# Arduino_Engine_Room.net
KiCad netlist of a schematic drawn in EAGLE
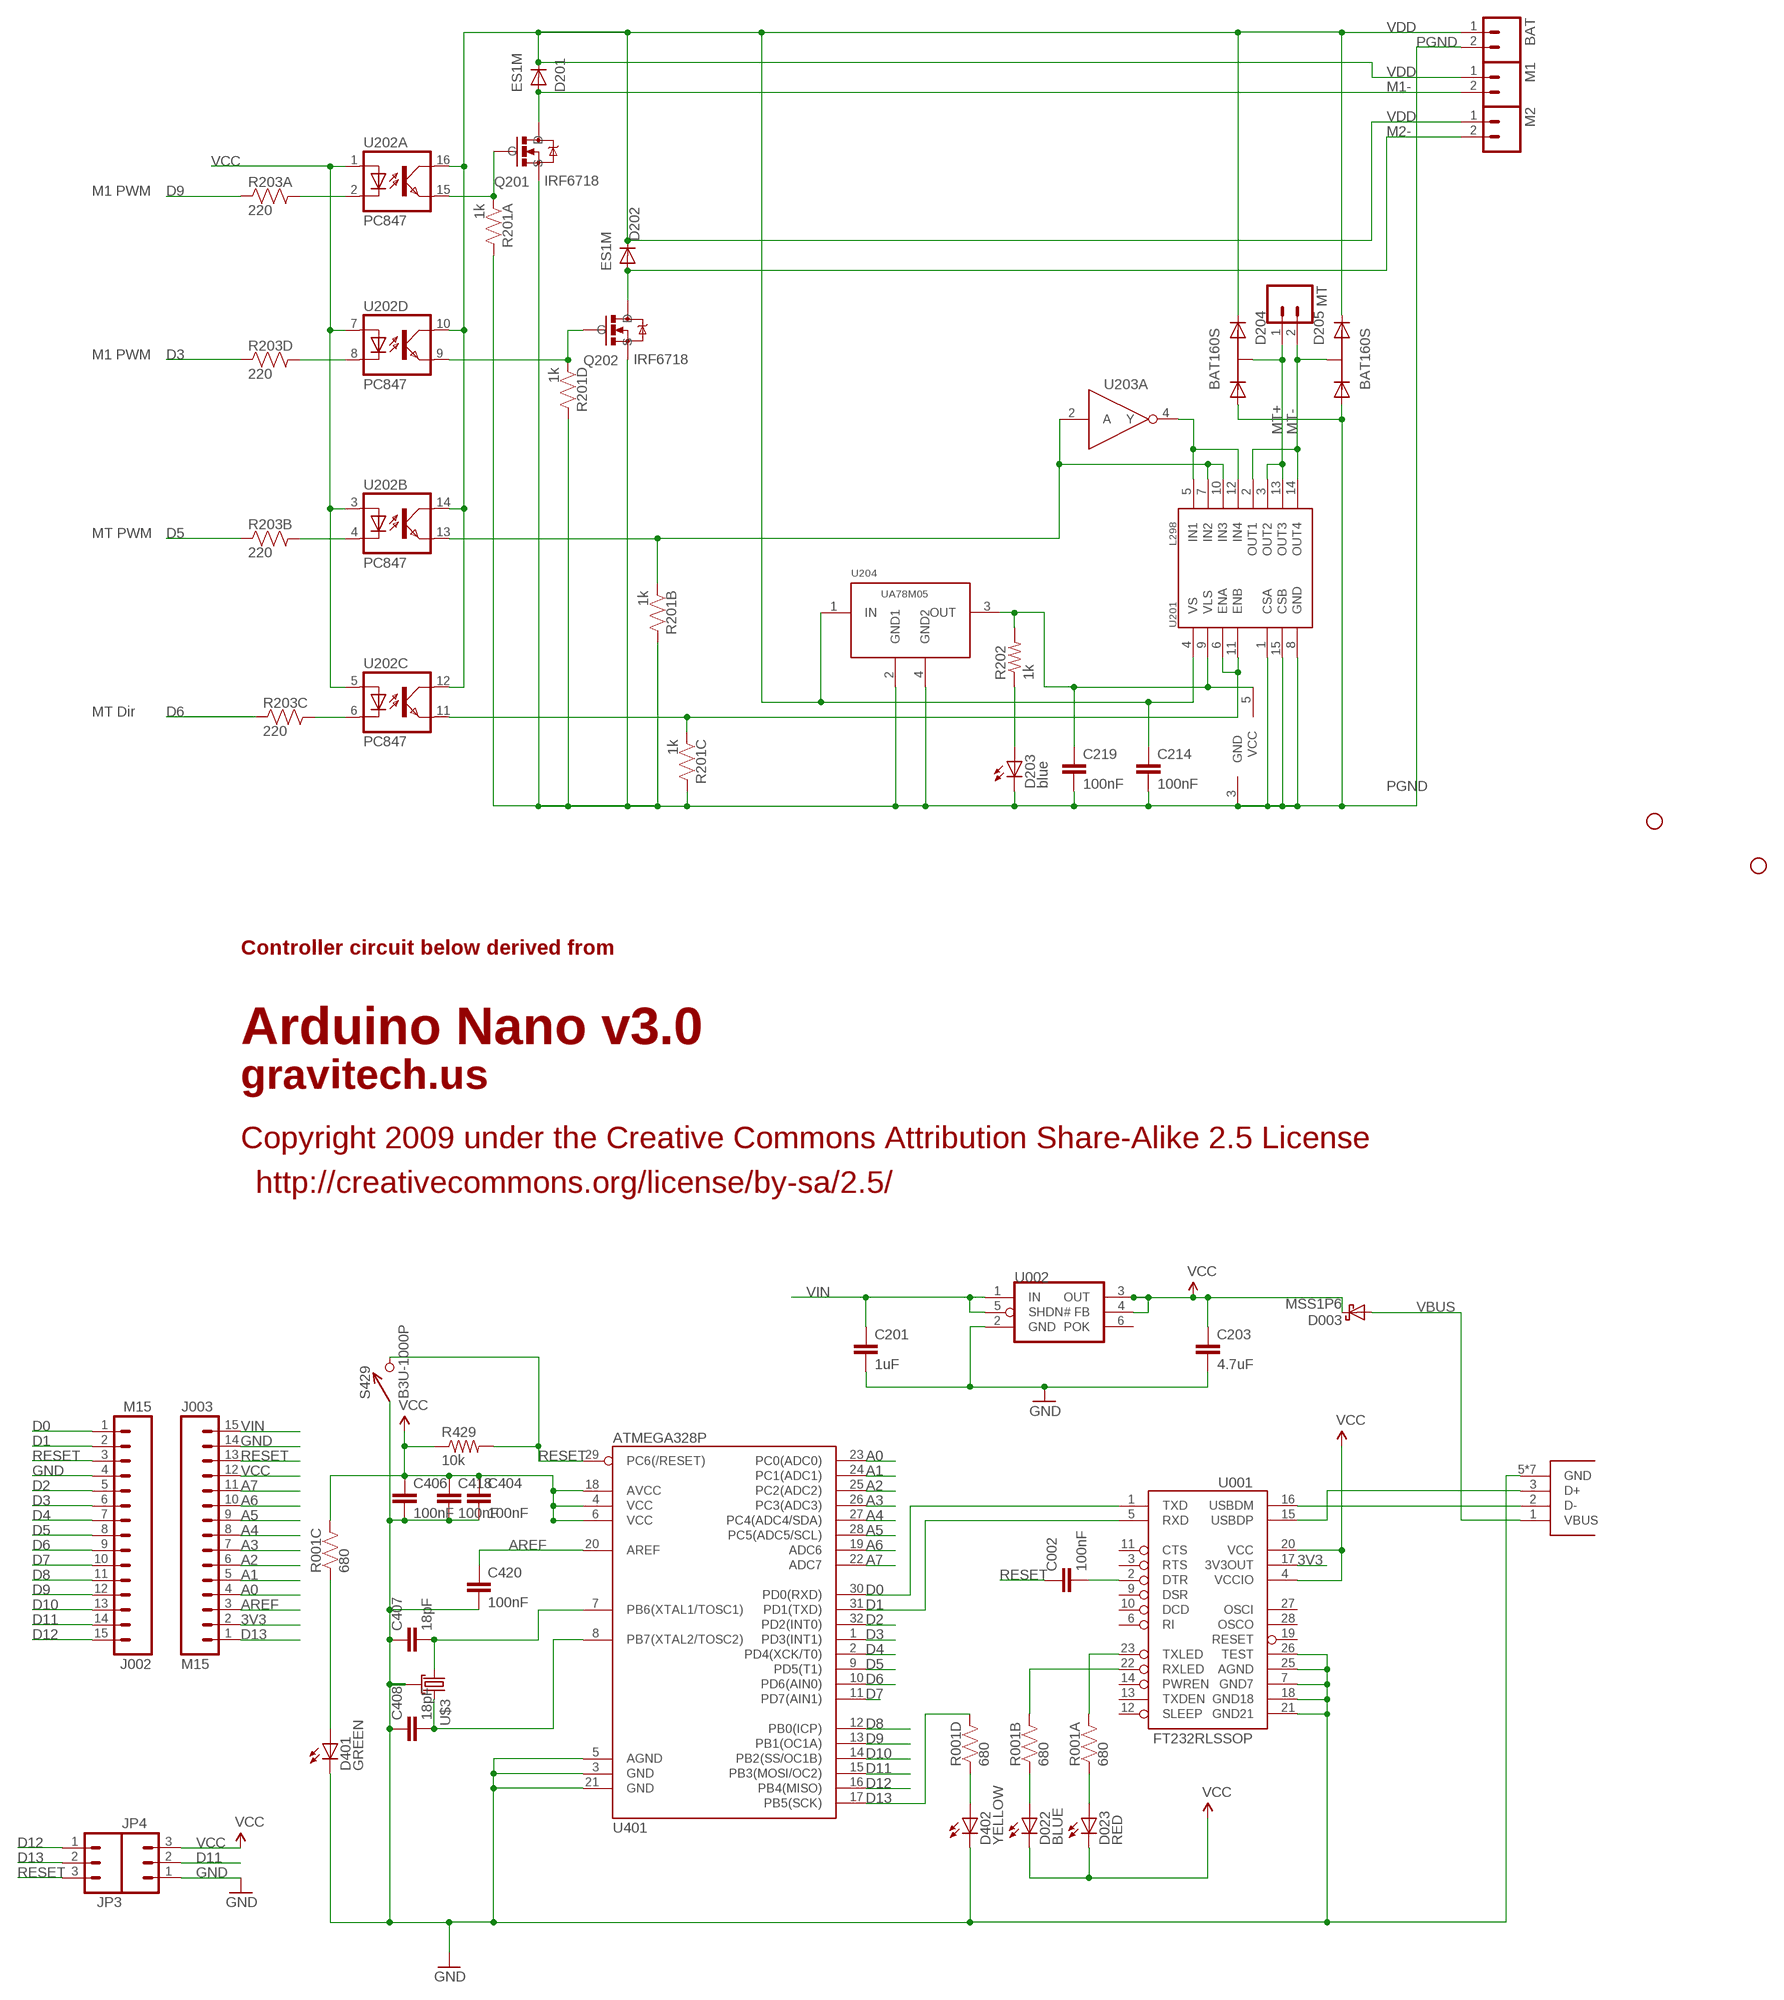
[diagram p0: schematic, sheet 1]

(export (version "E")
  (design (tool "Eeschema 10.0.6"))
  (components
    (comp (ref "BAT")
      (value "M02PTH4")
      (footprint "eagle-import:1X02_XTRA_BIG")
      (libsource (lib "eagle-import") (part "M02PTH4"))
    )
    (comp (ref "C002")
      (value "100nF")
      (footprint "eagle-import:0402-CAP")
      (libsource (lib "eagle-import") (part "CAP0402-CAP"))
    )
    (comp (ref "C201")
      (value "1uF")
      (footprint "eagle-import:0402-CAP")
      (libsource (lib "eagle-import") (part "CAP0402-CAP"))
    )
    (comp (ref "C203")
      (value "4.7uF")
      (footprint "eagle-import:0402-CAP")
      (libsource (lib "eagle-import") (part "CAP0402-CAP"))
    )
    (comp (ref "C214")
      (value "100nF")
      (footprint "eagle-import:0402-CAP")
      (libsource (lib "eagle-import") (part "CAP0402-CAP"))
    )
    (comp (ref "C219")
      (value "100nF")
      (footprint "eagle-import:0402-CAP")
      (libsource (lib "eagle-import") (part "CAP0402-CAP"))
    )
    (comp (ref "C404")
      (value "100nF")
      (footprint "eagle-import:0402-CAP")
      (libsource (lib "eagle-import") (part "CAP0402-CAP"))
    )
    (comp (ref "C406")
      (value "100nF")
      (footprint "eagle-import:0402-CAP")
      (libsource (lib "eagle-import") (part "CAP0402-CAP"))
    )
    (comp (ref "C407")
      (value "18pF")
      (footprint "eagle-import:0402-CAP")
      (libsource (lib "eagle-import") (part "CAP0402-CAP"))
    )
    (comp (ref "C408")
      (value "18pF")
      (footprint "eagle-import:0402-CAP")
      (libsource (lib "eagle-import") (part "CAP0402-CAP"))
    )
    (comp (ref "C418")
      (value "100nF")
      (footprint "eagle-import:0402-CAP")
      (libsource (lib "eagle-import") (part "CAP0402-CAP"))
    )
    (comp (ref "C420")
      (value "100nF")
      (footprint "eagle-import:0402-CAP")
      (libsource (lib "eagle-import") (part "CAP0402-CAP"))
    )
    (comp (ref "D003")
      (value "MSS1P6")
      (footprint "eagle-import:MICROSMP")
      (libsource (lib "eagle-import") (part "MSS1P6"))
    )
    (comp (ref "D022")
      (value "BLUE")
      (footprint "eagle-import:LED-0603")
      (libsource (lib "eagle-import") (part "SparkFun-LED_LED0603"))
    )
    (comp (ref "D023")
      (value "RED")
      (footprint "eagle-import:LED-0603")
      (libsource (lib "eagle-import") (part "SparkFun-LED_LED0603"))
    )
    (comp (ref "D201")
      (value "ES1M")
      (footprint "eagle-import:DO-214AC")
      (libsource (lib "eagle-import") (part "DIODE-DO-214AC"))
    )
    (comp (ref "D202")
      (value "ES1M")
      (footprint "eagle-import:DO-214AC")
      (libsource (lib "eagle-import") (part "DIODE-DO-214AC"))
    )
    (comp (ref "D203")
      (value "blue")
      (footprint "eagle-import:LED-0603")
      (libsource (lib "eagle-import") (part "LED0603"))
    )
    (comp (ref "D204")
      (value "BAT160S")
      (footprint "eagle-import:SOT-223")
      (libsource (lib "eagle-import") (part "BAT160S"))
    )
    (comp (ref "D205")
      (value "BAT160S")
      (footprint "eagle-import:SOT-223")
      (libsource (lib "eagle-import") (part "BAT160S"))
    )
    (comp (ref "D401")
      (value "GREEN")
      (footprint "eagle-import:LED-0603")
      (libsource (lib "eagle-import") (part "SparkFun-LED_LED0603"))
    )
    (comp (ref "D402")
      (value "YELLOW")
      (footprint "eagle-import:LED-0603")
      (libsource (lib "eagle-import") (part "SparkFun-LED_LED0603"))
    )
    (comp (ref "J001")
      (value "USB_MICROB_JST")
      (footprint "eagle-import:UB-MC5BR3-SD204-4S")
      (libsource (lib "eagle-import") (part "USB_MICROB_JST"))
    )
    (comp (ref "J002")
      (value "M15")
      (footprint "eagle-import:1X15")
      (libsource (lib "eagle-import") (part "M15"))
    )
    (comp (ref "J003")
      (value "M15")
      (footprint "eagle-import:1X15")
      (libsource (lib "eagle-import") (part "M15"))
    )
    (comp (ref "JP1")
      (value "STAND-OFF")
      (footprint "eagle-import:STAND-OFF")
      (libsource (lib "eagle-import") (part "STAND-OFF"))
    )
    (comp (ref "JP2")
      (value "STAND-OFF")
      (footprint "eagle-import:STAND-OFF")
      (libsource (lib "eagle-import") (part "STAND-OFF"))
    )
    (comp (ref "JP3")
      (value "M03PTH")
      (footprint "eagle-import:1X03")
      (libsource (lib "eagle-import") (part "M03PTH"))
    )
    (comp (ref "JP4")
      (value "M03PTH")
      (footprint "eagle-import:1X03")
      (libsource (lib "eagle-import") (part "M03PTH"))
    )
    (comp (ref "M1")
      (value "M02PTH4")
      (footprint "eagle-import:1X02_XTRA_BIG")
      (libsource (lib "eagle-import") (part "M02PTH4"))
    )
    (comp (ref "M2")
      (value "M02PTH4")
      (footprint "eagle-import:1X02_XTRA_BIG")
      (libsource (lib "eagle-import") (part "M02PTH4"))
    )
    (comp (ref "MT")
      (value "M02PTH")
      (footprint "eagle-import:1X02")
      (libsource (lib "eagle-import") (part "M02PTH"))
    )
    (comp (ref "Q201")
      (value "IRF6718")
      (footprint "eagle-import:DIRECTFET_L6")
      (libsource (lib "eagle-import") (part "IRF6718"))
    )
    (comp (ref "Q202")
      (value "IRF6718")
      (footprint "eagle-import:DIRECTFET_L6")
      (libsource (lib "eagle-import") (part "IRF6718"))
    )
    (comp (ref "R001")
      (value "680")
      (footprint "eagle-import:CRA04")
      (fields (field (name "DIGIKEY") "CRA4S8680CT-ND"))
      (libsource (lib "eagle-import") (part "RP404"))
    )
    (comp (ref "R201")
      (value "1k")
      (footprint "eagle-import:CRA04")
      (libsource (lib "eagle-import") (part "RP404"))
    )
    (comp (ref "R202")
      (value "1k")
      (footprint "eagle-import:0402-RES")
      (libsource (lib "eagle-import") (part "RESISTOR0402-RES"))
    )
    (comp (ref "R203")
      (value "220")
      (footprint "eagle-import:CRA04")
      (libsource (lib "eagle-import") (part "RP404"))
    )
    (comp (ref "R429")
      (value "10k")
      (footprint "eagle-import:0402-RES")
      (libsource (lib "eagle-import") (part "SparkFun-Passives_RESISTOR0402-RES"))
    )
    (comp (ref "S429")
      (value "B3U-1000P")
      (footprint "eagle-import:B3U-1000P")
      (libsource (lib "eagle-import") (part "B3U-1000P"))
    )
    (comp (ref "U$3")
      (value "CX2520")
      (footprint "eagle-import:CRYSTAL_SMD_2MM_2_5MM")
      (libsource (lib "eagle-import") (part "CX2520"))
    )
    (comp (ref "U001")
      (value "FT232RLSSOP")
      (footprint "eagle-import:SSOP28DB")
      (libsource (lib "eagle-import") (part "FT232RLSSOP"))
    )
    (comp (ref "U002")
      (value "MAX8881")
      (footprint "eagle-import:SOT-23-6")
      (libsource (lib "eagle-import") (part "MAX8881"))
    )
    (comp (ref "U201")
      (value "L298")
      (footprint "eagle-import:MULTIWATT15")
      (libsource (lib "eagle-import") (part "L298"))
    )
    (comp (ref "U202")
      (value "PC847")
      (footprint "eagle-import:DIL16")
      (libsource (lib "eagle-import") (part "PC847"))
    )
    (comp (ref "U203")
      (value "MC74VHC1G04")
      (footprint "eagle-import:SOT-23-5")
      (libsource (lib "eagle-import") (part "MC74VHC1G04"))
    )
    (comp (ref "U204")
      (value "UA78M05")
      (footprint "eagle-import:SOT223")
      (libsource (lib "eagle-import") (part "UA78M05"))
    )
    (comp (ref "U401")
      (value "ATMEGA328P")
      (footprint "eagle-import:TQFP32-08")
      (libsource (lib "eagle-import") (part "ATMEGA168"))
    )
  )
  (nets
    (net (code "1") (name "/3V3") (class "Default")
      (node (ref "J003") (pin "2") (pinfunction "2_2") (pintype "passive"))
      (node (ref "U001") (pin "17") (pinfunction "3V3OUT_17") (pintype "output"))
    )
    (net (code "2") (name "/A0") (class "Default")
      (node (ref "J003") (pin "4") (pinfunction "4_4") (pintype "passive"))
      (node (ref "U401") (pin "23") (pinfunction "PC0(ADC0)_23") (pintype "bidirectional"))
    )
    (net (code "3") (name "/A1") (class "Default")
      (node (ref "J003") (pin "5") (pinfunction "5_5") (pintype "passive"))
      (node (ref "U401") (pin "24") (pinfunction "PC1(ADC1)_24") (pintype "bidirectional"))
    )
    (net (code "4") (name "/A2") (class "Default")
      (node (ref "J003") (pin "6") (pinfunction "6_6") (pintype "passive"))
      (node (ref "U401") (pin "25") (pinfunction "PC2(ADC2)_25") (pintype "bidirectional"))
    )
    (net (code "5") (name "/A3") (class "Default")
      (node (ref "J003") (pin "7") (pinfunction "7_7") (pintype "passive"))
      (node (ref "U401") (pin "26") (pinfunction "PC3(ADC3)_26") (pintype "bidirectional"))
    )
    (net (code "6") (name "/A4") (class "Default")
      (node (ref "J003") (pin "8") (pinfunction "8_8") (pintype "passive"))
      (node (ref "U401") (pin "27") (pinfunction "PC4(ADC4/SDA)_27") (pintype "bidirectional"))
    )
    (net (code "7") (name "/A5") (class "Default")
      (node (ref "J003") (pin "9") (pinfunction "9_9") (pintype "passive"))
      (node (ref "U401") (pin "28") (pinfunction "PC5(ADC5/SCL)_28") (pintype "bidirectional"))
    )
    (net (code "8") (name "/A6") (class "Default")
      (node (ref "J003") (pin "10") (pinfunction "10_10") (pintype "passive"))
      (node (ref "U401") (pin "19") (pinfunction "ADC6_19") (pintype "bidirectional"))
    )
    (net (code "9") (name "/A7") (class "Default")
      (node (ref "J003") (pin "11") (pinfunction "11_11") (pintype "passive"))
      (node (ref "U401") (pin "22") (pinfunction "ADC7_22") (pintype "bidirectional"))
    )
    (net (code "10") (name "/AREF") (class "Default")
      (node (ref "C420") (pin "1") (pinfunction "1_1") (pintype "passive"))
      (node (ref "J003") (pin "3") (pinfunction "3_3") (pintype "passive"))
      (node (ref "U401") (pin "20") (pinfunction "AREF_20") (pintype "bidirectional"))
    )
    (net (code "11") (name "/D0") (class "Default")
      (node (ref "J002") (pin "1") (pinfunction "1_1") (pintype "passive"))
      (node (ref "U001") (pin "1") (pinfunction "TXD_1") (pintype "output"))
      (node (ref "U401") (pin "30") (pinfunction "PD0(RXD)_30") (pintype "bidirectional"))
    )
    (net (code "12") (name "/D1") (class "Default")
      (node (ref "J002") (pin "2") (pinfunction "2_2") (pintype "passive"))
      (node (ref "U001") (pin "5") (pinfunction "RXD_5") (pintype "input"))
      (node (ref "U401") (pin "31") (pinfunction "PD1(TXD)_31") (pintype "bidirectional"))
    )
    (net (code "13") (name "/D2") (class "Default")
      (node (ref "J002") (pin "5") (pinfunction "5_5") (pintype "passive"))
      (node (ref "U401") (pin "32") (pinfunction "PD2(INT0)_32") (pintype "bidirectional"))
    )
    (net (code "14") (name "/D3") (class "Default")
      (node (ref "J002") (pin "6") (pinfunction "6_6") (pintype "passive"))
      (node (ref "R203") (pin "4") (pinfunction "1_4") (pintype "passive"))
      (node (ref "U401") (pin "1") (pinfunction "PD3(INT1)_1") (pintype "bidirectional"))
    )
    (net (code "15") (name "/D4") (class "Default")
      (node (ref "J002") (pin "7") (pinfunction "7_7") (pintype "passive"))
      (node (ref "U401") (pin "2") (pinfunction "PD4(XCK/T0)_2") (pintype "bidirectional"))
    )
    (net (code "16") (name "/D5") (class "Default")
      (node (ref "J002") (pin "8") (pinfunction "8_8") (pintype "passive"))
      (node (ref "R203") (pin "2") (pinfunction "1_2") (pintype "passive"))
      (node (ref "U401") (pin "9") (pinfunction "PD5(T1)_9") (pintype "bidirectional"))
    )
    (net (code "17") (name "/D6") (class "Default")
      (node (ref "J002") (pin "9") (pinfunction "9_9") (pintype "passive"))
      (node (ref "R203") (pin "3") (pinfunction "1_3") (pintype "passive"))
      (node (ref "U401") (pin "10") (pinfunction "PD6(AIN0)_10") (pintype "bidirectional"))
    )
    (net (code "18") (name "/D7") (class "Default")
      (node (ref "J002") (pin "10") (pinfunction "10_10") (pintype "passive"))
      (node (ref "U401") (pin "11") (pinfunction "PD7(AIN1)_11") (pintype "bidirectional"))
    )
    (net (code "19") (name "/D8") (class "Default")
      (node (ref "J002") (pin "11") (pinfunction "11_11") (pintype "passive"))
      (node (ref "U401") (pin "12") (pinfunction "PB0(ICP)_12") (pintype "bidirectional"))
    )
    (net (code "20") (name "/D9") (class "Default")
      (node (ref "J002") (pin "12") (pinfunction "12_12") (pintype "passive"))
      (node (ref "R203") (pin "1") (pinfunction "1_1") (pintype "passive"))
      (node (ref "U401") (pin "13") (pinfunction "PB1(OC1A)_13") (pintype "bidirectional"))
    )
    (net (code "21") (name "/D10") (class "Default")
      (node (ref "J002") (pin "13") (pinfunction "13_13") (pintype "passive"))
      (node (ref "U401") (pin "14") (pinfunction "PB2(SS/OC1B)_14") (pintype "bidirectional"))
    )
    (net (code "22") (name "/D11") (class "Default")
      (node (ref "J002") (pin "14") (pinfunction "14_14") (pintype "passive"))
      (node (ref "JP4") (pin "2") (pinfunction "2_2") (pintype "passive"))
      (node (ref "U401") (pin "15") (pinfunction "PB3(MOSI/OC2)_15") (pintype "bidirectional"))
    )
    (net (code "23") (name "/D12") (class "Default")
      (node (ref "J002") (pin "15") (pinfunction "15_15") (pintype "passive"))
      (node (ref "JP3") (pin "1") (pinfunction "1_1") (pintype "passive"))
      (node (ref "U401") (pin "16") (pinfunction "PB4(MISO)_16") (pintype "bidirectional"))
    )
    (net (code "24") (name "/D13") (class "Default")
      (node (ref "J003") (pin "1") (pinfunction "1_1") (pintype "passive"))
      (node (ref "JP3") (pin "2") (pinfunction "2_2") (pintype "passive"))
      (node (ref "R001") (pin "5") (pinfunction "2_5") (pintype "passive"))
      (node (ref "U401") (pin "17") (pinfunction "PB5(SCK)_17") (pintype "bidirectional"))
    )
    (net (code "25") (name "/M1-") (class "Default")
      (node (ref "D201") (pin "A") (pinfunction "A_A") (pintype "passive"))
      (node (ref "M1") (pin "2") (pinfunction "2_2") (pintype "passive"))
      (node (ref "Q201") (pin "D1") (pinfunction "D_D1") (pintype "passive"))
      (node (ref "Q201") (pin "D2") (pinfunction "D_D2") (pintype "passive"))
    )
    (net (code "26") (name "/M2-") (class "Default")
      (node (ref "D202") (pin "A") (pinfunction "A_A") (pintype "passive"))
      (node (ref "M2") (pin "2") (pinfunction "2_2") (pintype "passive"))
      (node (ref "Q202") (pin "D1") (pinfunction "D_D1") (pintype "passive"))
      (node (ref "Q202") (pin "D2") (pinfunction "D_D2") (pintype "passive"))
    )
    (net (code "27") (name "/MT+") (class "Default")
      (node (ref "D204") (pin "4") (pinfunction "K1A2_4") (pintype "passive"))
      (node (ref "MT") (pin "1") (pinfunction "1_1") (pintype "passive"))
      (node (ref "U201") (pin "13") (pinfunction "OUT3_13") (pintype "bidirectional"))
      (node (ref "U201") (pin "3") (pinfunction "OUT2_3") (pintype "bidirectional"))
    )
    (net (code "28") (name "/MT-") (class "Default")
      (node (ref "D205") (pin "4") (pinfunction "K1A2_4") (pintype "passive"))
      (node (ref "MT") (pin "2") (pinfunction "2_2") (pintype "passive"))
      (node (ref "U201") (pin "14") (pinfunction "OUT4_14") (pintype "bidirectional"))
      (node (ref "U201") (pin "2") (pinfunction "OUT1_2") (pintype "bidirectional"))
    )
    (net (code "29") (name "/PGND") (class "Default")
      (node (ref "BAT") (pin "2") (pinfunction "2_2") (pintype "passive"))
      (node (ref "C214") (pin "2") (pinfunction "2_2") (pintype "passive"))
      (node (ref "C219") (pin "2") (pinfunction "2_2") (pintype "passive"))
      (node (ref "D203") (pin "C") (pinfunction "C_C") (pintype "passive"))
      (node (ref "D204") (pin "1") (pinfunction "A1_1") (pintype "passive"))
      (node (ref "D205") (pin "1") (pinfunction "A1_1") (pintype "passive"))
      (node (ref "Q201") (pin "S") (pinfunction "S_S") (pintype "passive"))
      (node (ref "Q202") (pin "S") (pinfunction "S_S") (pintype "passive"))
      (node (ref "R201") (pin "5") (pinfunction "2_5") (pintype "passive"))
      (node (ref "R201") (pin "6") (pinfunction "2_6") (pintype "passive"))
      (node (ref "R201") (pin "7") (pinfunction "2_7") (pintype "passive"))
      (node (ref "R201") (pin "8") (pinfunction "2_8") (pintype "passive"))
      (node (ref "U201") (pin "1") (pinfunction "CSA_1") (pintype "bidirectional"))
      (node (ref "U201") (pin "15") (pinfunction "CSB_15") (pintype "bidirectional"))
      (node (ref "U201") (pin "8") (pinfunction "GND_8") (pintype "bidirectional"))
      (node (ref "U203") (pin "3") (pinfunction "GND_3") (pintype "bidirectional"))
      (node (ref "U204") (pin "2") (pinfunction "GND1_2") (pintype "power_in"))
      (node (ref "U204") (pin "4") (pinfunction "GND2_4") (pintype "power_in"))
    )
    (net (code "30") (name "/RESET") (class "Default")
      (node (ref "C002") (pin "1") (pinfunction "1_1") (pintype "passive"))
      (node (ref "J002") (pin "3") (pinfunction "3_3") (pintype "passive"))
      (node (ref "J003") (pin "13") (pinfunction "13_13") (pintype "passive"))
      (node (ref "JP3") (pin "3") (pinfunction "3_3") (pintype "passive"))
      (node (ref "R429") (pin "2") (pinfunction "2_2") (pintype "passive"))
      (node (ref "S429") (pin "P$2") (pinfunction "2_P$2") (pintype "bidirectional"))
      (node (ref "U401") (pin "29") (pinfunction "PC6(/RESET)_29") (pintype "bidirectional"))
    )
    (net (code "31") (name "/VBUS") (class "Default")
      (node (ref "D003") (pin "A") (pinfunction "A_A") (pintype "passive"))
      (node (ref "J001") (pin "1") (pinfunction "VBUS_1") (pintype "bidirectional"))
    )
    (net (code "32") (name "/VDD") (class "Default")
      (node (ref "BAT") (pin "1") (pinfunction "1_1") (pintype "passive"))
      (node (ref "C214") (pin "1") (pinfunction "1_1") (pintype "passive"))
      (node (ref "D201") (pin "C") (pinfunction "C_C") (pintype "passive"))
      (node (ref "D202") (pin "C") (pinfunction "C_C") (pintype "passive"))
      (node (ref "D204") (pin "3") (pinfunction "K2_3") (pintype "passive"))
      (node (ref "D205") (pin "3") (pinfunction "K2_3") (pintype "passive"))
      (node (ref "M1") (pin "1") (pinfunction "1_1") (pintype "passive"))
      (node (ref "M2") (pin "1") (pinfunction "1_1") (pintype "passive"))
      (node (ref "U201") (pin "4") (pinfunction "VS_4") (pintype "bidirectional"))
      (node (ref "U202") (pin "10") (pinfunction "COL_10") (pintype "passive"))
      (node (ref "U202") (pin "12") (pinfunction "COL_12") (pintype "passive"))
      (node (ref "U202") (pin "14") (pinfunction "COL_14") (pintype "passive"))
      (node (ref "U202") (pin "16") (pinfunction "COL_16") (pintype "passive"))
      (node (ref "U204") (pin "1") (pinfunction "IN_1") (pintype "power_in"))
    )
    (net (code "33") (name "/VIN") (class "Default")
      (node (ref "C201") (pin "1") (pinfunction "1_1") (pintype "passive"))
      (node (ref "J003") (pin "15") (pinfunction "15_15") (pintype "passive"))
      (node (ref "U002") (pin "1") (pinfunction "IN_1") (pintype "bidirectional"))
      (node (ref "U002") (pin "5") (pinfunction "SHDN#_5") (pintype "bidirectional"))
    )
    (net (code "34") (name "GND") (class "Default")
      (node (ref "C201") (pin "2") (pinfunction "2_2") (pintype "passive"))
      (node (ref "C203") (pin "2") (pinfunction "2_2") (pintype "passive"))
      (node (ref "C404") (pin "2") (pinfunction "2_2") (pintype "passive"))
      (node (ref "C406") (pin "2") (pinfunction "2_2") (pintype "passive"))
      (node (ref "C407") (pin "1") (pinfunction "1_1") (pintype "passive"))
      (node (ref "C408") (pin "1") (pinfunction "1_1") (pintype "passive"))
      (node (ref "C418") (pin "2") (pinfunction "2_2") (pintype "passive"))
      (node (ref "C420") (pin "2") (pinfunction "2_2") (pintype "passive"))
      (node (ref "D401") (pin "C") (pinfunction "C_C") (pintype "passive"))
      (node (ref "D402") (pin "C") (pinfunction "C_C") (pintype "passive"))
      (node (ref "J001") (pin "5") (pinfunction "GND_5") (pintype "bidirectional"))
      (node (ref "J001") (pin "P$10") (pinfunction "GND_P$10") (pintype "bidirectional"))
      (node (ref "J001") (pin "P$11") (pinfunction "GND_P$11") (pintype "bidirectional"))
      (node (ref "J001") (pin "P$6") (pinfunction "GND_P$6") (pintype "bidirectional"))
      (node (ref "J001") (pin "P$7") (pinfunction "GND_P$7") (pintype "bidirectional"))
      (node (ref "J001") (pin "P$8") (pinfunction "GND_P$8") (pintype "bidirectional"))
      (node (ref "J001") (pin "P$9") (pinfunction "GND_P$9") (pintype "bidirectional"))
      (node (ref "J002") (pin "4") (pinfunction "4_4") (pintype "passive"))
      (node (ref "J003") (pin "14") (pinfunction "14_14") (pintype "passive"))
      (node (ref "JP4") (pin "1") (pinfunction "1_1") (pintype "passive"))
      (node (ref "S429") (pin "P$1") (pinfunction "1_P$1") (pintype "bidirectional"))
      (node (ref "U$3") (pin "2") (pinfunction "P$1_2") (pintype "passive"))
      (node (ref "U$3") (pin "4") (pinfunction "P$1_4") (pintype "passive"))
      (node (ref "U001") (pin "18") (pinfunction "GND18_18") (pintype "power_in"))
      (node (ref "U001") (pin "21") (pinfunction "GND21_21") (pintype "power_in"))
      (node (ref "U001") (pin "25") (pinfunction "AGND_25") (pintype "power_in"))
      (node (ref "U001") (pin "26") (pinfunction "TEST_26") (pintype "input"))
      (node (ref "U001") (pin "7") (pinfunction "GND7_7") (pintype "power_in"))
      (node (ref "U002") (pin "2") (pinfunction "GND_2") (pintype "bidirectional"))
      (node (ref "U401") (pin "21") (pinfunction "GND_21") (pintype "bidirectional"))
      (node (ref "U401") (pin "3") (pinfunction "GND_3") (pintype "bidirectional"))
      (node (ref "U401") (pin "5") (pinfunction "AGND_5") (pintype "bidirectional"))
    )
    (net (code "35") (name "Net-(D023-PadA)") (class "Default")
      (node (ref "D023") (pin "A") (pinfunction "A_A") (pintype "passive"))
      (node (ref "R001") (pin "1") (pinfunction "1_1") (pintype "passive"))
    )
    (net (code "36") (name "Net-(D203-PadA)") (class "Default")
      (node (ref "D203") (pin "A") (pinfunction "A_A") (pintype "passive"))
      (node (ref "R202") (pin "1") (pinfunction "1_1") (pintype "passive"))
    )
    (net (code "37") (name "Net-(J001-D+)") (class "Default")
      (node (ref "J001") (pin "3") (pinfunction "D+_3") (pintype "bidirectional"))
      (node (ref "U001") (pin "15") (pinfunction "USBDP_15") (pintype "bidirectional"))
    )
    (net (code "38") (name "Net-(J001-D-)") (class "Default")
      (node (ref "J001") (pin "2") (pinfunction "D-_2") (pintype "bidirectional"))
      (node (ref "U001") (pin "16") (pinfunction "USBDM_16") (pintype "bidirectional"))
    )
    (net (code "39") (name "Net-(R001A-2)") (class "Default")
      (node (ref "R001") (pin "8") (pinfunction "2_8") (pintype "passive"))
      (node (ref "U001") (pin "23") (pinfunction "TXLED_23") (pintype "input"))
    )
    (net (code "40") (name "Net-(R001B-1)") (class "Default")
      (node (ref "D022") (pin "A") (pinfunction "A_A") (pintype "passive"))
      (node (ref "R001") (pin "2") (pinfunction "1_2") (pintype "passive"))
    )
    (net (code "41") (name "Net-(R001B-2)") (class "Default")
      (node (ref "R001") (pin "7") (pinfunction "2_7") (pintype "passive"))
      (node (ref "U001") (pin "22") (pinfunction "RXLED_22") (pintype "input"))
    )
    (net (code "42") (name "Net-(R001C-1)") (class "Default")
      (node (ref "D401") (pin "A") (pinfunction "A_A") (pintype "passive"))
      (node (ref "R001") (pin "3") (pinfunction "1_3") (pintype "passive"))
    )
    (net (code "43") (name "Net-(R001D-1)") (class "Default")
      (node (ref "D402") (pin "A") (pinfunction "A_A") (pintype "passive"))
      (node (ref "R001") (pin "4") (pinfunction "1_4") (pintype "passive"))
    )
    (net (code "44") (name "Net-(R201B-1)") (class "Default")
      (node (ref "R201") (pin "2") (pinfunction "1_2") (pintype "passive"))
      (node (ref "U201") (pin "10") (pinfunction "IN3_10") (pintype "bidirectional"))
      (node (ref "U201") (pin "7") (pinfunction "IN2_7") (pintype "bidirectional"))
      (node (ref "U202") (pin "13") (pinfunction "EMIT_13") (pintype "passive"))
      (node (ref "U203") (pin "2") (pinfunction "A_2") (pintype "bidirectional"))
    )
    (net (code "45") (name "Net-(R201C-1)") (class "Default")
      (node (ref "R201") (pin "3") (pinfunction "1_3") (pintype "passive"))
      (node (ref "U201") (pin "11") (pinfunction "ENB_11") (pintype "bidirectional"))
      (node (ref "U201") (pin "6") (pinfunction "ENA_6") (pintype "bidirectional"))
      (node (ref "U202") (pin "11") (pinfunction "EMIT_11") (pintype "passive"))
    )
    (net (code "46") (name "Net-(R201D-1)") (class "Default")
      (node (ref "Q202") (pin "G") (pinfunction "G_G") (pintype "passive"))
      (node (ref "R201") (pin "4") (pinfunction "1_4") (pintype "passive"))
      (node (ref "U202") (pin "9") (pinfunction "EMIT_9") (pintype "passive"))
    )
    (net (code "47") (name "Net-(R203A-2)") (class "Default")
      (node (ref "R203") (pin "8") (pinfunction "2_8") (pintype "passive"))
      (node (ref "U202") (pin "2") (pinfunction "C_2") (pintype "passive"))
    )
    (net (code "48") (name "Net-(R203B-2)") (class "Default")
      (node (ref "R203") (pin "7") (pinfunction "2_7") (pintype "passive"))
      (node (ref "U202") (pin "4") (pinfunction "C_4") (pintype "passive"))
    )
    (net (code "49") (name "Net-(R203C-2)") (class "Default")
      (node (ref "R203") (pin "6") (pinfunction "2_6") (pintype "passive"))
      (node (ref "U202") (pin "6") (pinfunction "C_6") (pintype "passive"))
    )
    (net (code "50") (name "Net-(R203D-2)") (class "Default")
      (node (ref "R203") (pin "5") (pinfunction "2_5") (pintype "passive"))
      (node (ref "U202") (pin "8") (pinfunction "C_8") (pintype "passive"))
    )
    (net (code "51") (name "Net-(U$3-2)") (class "Default")
      (node (ref "C408") (pin "2") (pinfunction "2_2") (pintype "passive"))
      (node (ref "U$3") (pin "3") (pinfunction "2_3") (pintype "passive"))
      (node (ref "U401") (pin "8") (pinfunction "PB7(XTAL2/TOSC2)_8") (pintype "bidirectional"))
    )
    (net (code "52") (name "Net-(U001-DTR)") (class "Default")
      (node (ref "C002") (pin "2") (pinfunction "2_2") (pintype "passive"))
      (node (ref "U001") (pin "2") (pinfunction "DTR_2") (pintype "output"))
    )
    (net (code "53") (name "Net-(U201-IN1)") (class "Default")
      (node (ref "U201") (pin "12") (pinfunction "IN4_12") (pintype "bidirectional"))
      (node (ref "U201") (pin "5") (pinfunction "IN1_5") (pintype "bidirectional"))
      (node (ref "U203") (pin "4") (pinfunction "Y_4") (pintype "bidirectional"))
    )
    (net (code "54") (name "Net-(U201-VLS)") (class "Default")
      (node (ref "C219") (pin "1") (pinfunction "1_1") (pintype "passive"))
      (node (ref "R202") (pin "2") (pinfunction "2_2") (pintype "passive"))
      (node (ref "U201") (pin "9") (pinfunction "VLS_9") (pintype "bidirectional"))
      (node (ref "U203") (pin "5") (pinfunction "VCC_5") (pintype "bidirectional"))
      (node (ref "U204") (pin "3") (pinfunction "OUT_3") (pintype "power_in"))
    )
    (net (code "55") (name "Net-(U202A-EMIT)") (class "Default")
      (node (ref "Q201") (pin "G") (pinfunction "G_G") (pintype "passive"))
      (node (ref "R201") (pin "1") (pinfunction "1_1") (pintype "passive"))
      (node (ref "U202") (pin "15") (pinfunction "EMIT_15") (pintype "passive"))
    )
    (net (code "56") (name "Net-(U401-PB6(XTAL1{slash}TOSC1))") (class "Default")
      (node (ref "C407") (pin "2") (pinfunction "2_2") (pintype "passive"))
      (node (ref "U$3") (pin "1") (pinfunction "1_1") (pintype "passive"))
      (node (ref "U401") (pin "7") (pinfunction "PB6(XTAL1/TOSC1)_7") (pintype "bidirectional"))
    )
    (net (code "57") (name "VCC") (class "Default")
      (node (ref "C203") (pin "1") (pinfunction "1_1") (pintype "passive"))
      (node (ref "C404") (pin "1") (pinfunction "1_1") (pintype "passive"))
      (node (ref "C406") (pin "1") (pinfunction "1_1") (pintype "passive"))
      (node (ref "C418") (pin "1") (pinfunction "1_1") (pintype "passive"))
      (node (ref "D003") (pin "K") (pinfunction "K_K") (pintype "passive"))
      (node (ref "D022") (pin "C") (pinfunction "C_C") (pintype "passive"))
      (node (ref "D023") (pin "C") (pinfunction "C_C") (pintype "passive"))
      (node (ref "J003") (pin "12") (pinfunction "12_12") (pintype "passive"))
      (node (ref "JP4") (pin "3") (pinfunction "3_3") (pintype "passive"))
      (node (ref "R001") (pin "6") (pinfunction "2_6") (pintype "passive"))
      (node (ref "R429") (pin "1") (pinfunction "1_1") (pintype "passive"))
      (node (ref "U001") (pin "20") (pinfunction "VCC_20") (pintype "power_in"))
      (node (ref "U001") (pin "4") (pinfunction "VCCIO_4") (pintype "power_in"))
      (node (ref "U002") (pin "3") (pinfunction "OUT_3") (pintype "bidirectional"))
      (node (ref "U002") (pin "4") (pinfunction "FB_4") (pintype "bidirectional"))
      (node (ref "U202") (pin "1") (pinfunction "A_1") (pintype "passive"))
      (node (ref "U202") (pin "3") (pinfunction "A_3") (pintype "passive"))
      (node (ref "U202") (pin "5") (pinfunction "A_5") (pintype "passive"))
      (node (ref "U202") (pin "7") (pinfunction "A_7") (pintype "passive"))
      (node (ref "U401") (pin "18") (pinfunction "AVCC_18") (pintype "bidirectional"))
      (node (ref "U401") (pin "4") (pinfunction "VCC_4") (pintype "bidirectional"))
      (node (ref "U401") (pin "6") (pinfunction "VCC_6") (pintype "bidirectional"))
    )
    (net (code "58") (name "unconnected-(U001-CTS-Pad11)") (class "Default")
      (node (ref "U001") (pin "11") (pinfunction "CTS_11") (pintype "input"))
    )
    (net (code "59") (name "unconnected-(U001-DCD-Pad10)") (class "Default")
      (node (ref "U001") (pin "10") (pinfunction "DCD_10") (pintype "input"))
    )
    (net (code "60") (name "unconnected-(U001-DSR-Pad9)") (class "Default")
      (node (ref "U001") (pin "9") (pinfunction "DSR_9") (pintype "input"))
    )
    (net (code "61") (name "unconnected-(U001-OSCI-Pad27)") (class "Default")
      (node (ref "U001") (pin "27") (pinfunction "OSCI_27") (pintype "input"))
    )
    (net (code "62") (name "unconnected-(U001-OSCO-Pad28)") (class "Default")
      (node (ref "U001") (pin "28") (pinfunction "OSCO_28") (pintype "output"))
    )
    (net (code "63") (name "unconnected-(U001-PWREN-Pad14)") (class "Default")
      (node (ref "U001") (pin "14") (pinfunction "PWREN_14") (pintype "input"))
    )
    (net (code "64") (name "unconnected-(U001-RESET-Pad19)") (class "Default")
      (node (ref "U001") (pin "19") (pinfunction "RESET_19") (pintype "input"))
    )
    (net (code "65") (name "unconnected-(U001-RI-Pad6)") (class "Default")
      (node (ref "U001") (pin "6") (pinfunction "RI_6") (pintype "input"))
    )
    (net (code "66") (name "unconnected-(U001-RTS-Pad3)") (class "Default")
      (node (ref "U001") (pin "3") (pinfunction "RTS_3") (pintype "output"))
    )
    (net (code "67") (name "unconnected-(U001-SLEEP-Pad12)") (class "Default")
      (node (ref "U001") (pin "12") (pinfunction "SLEEP_12") (pintype "input"))
    )
    (net (code "68") (name "unconnected-(U001-TXDEN-Pad13)") (class "Default")
      (node (ref "U001") (pin "13") (pinfunction "TXDEN_13") (pintype "input"))
    )
    (net (code "69") (name "unconnected-(U002-POK-Pad6)") (class "Default")
      (node (ref "U002") (pin "6") (pinfunction "POK_6") (pintype "bidirectional"))
    )
  )
)
